# esp8266_analog_read.net
KiCad netlist of a schematic drawn in EAGLE
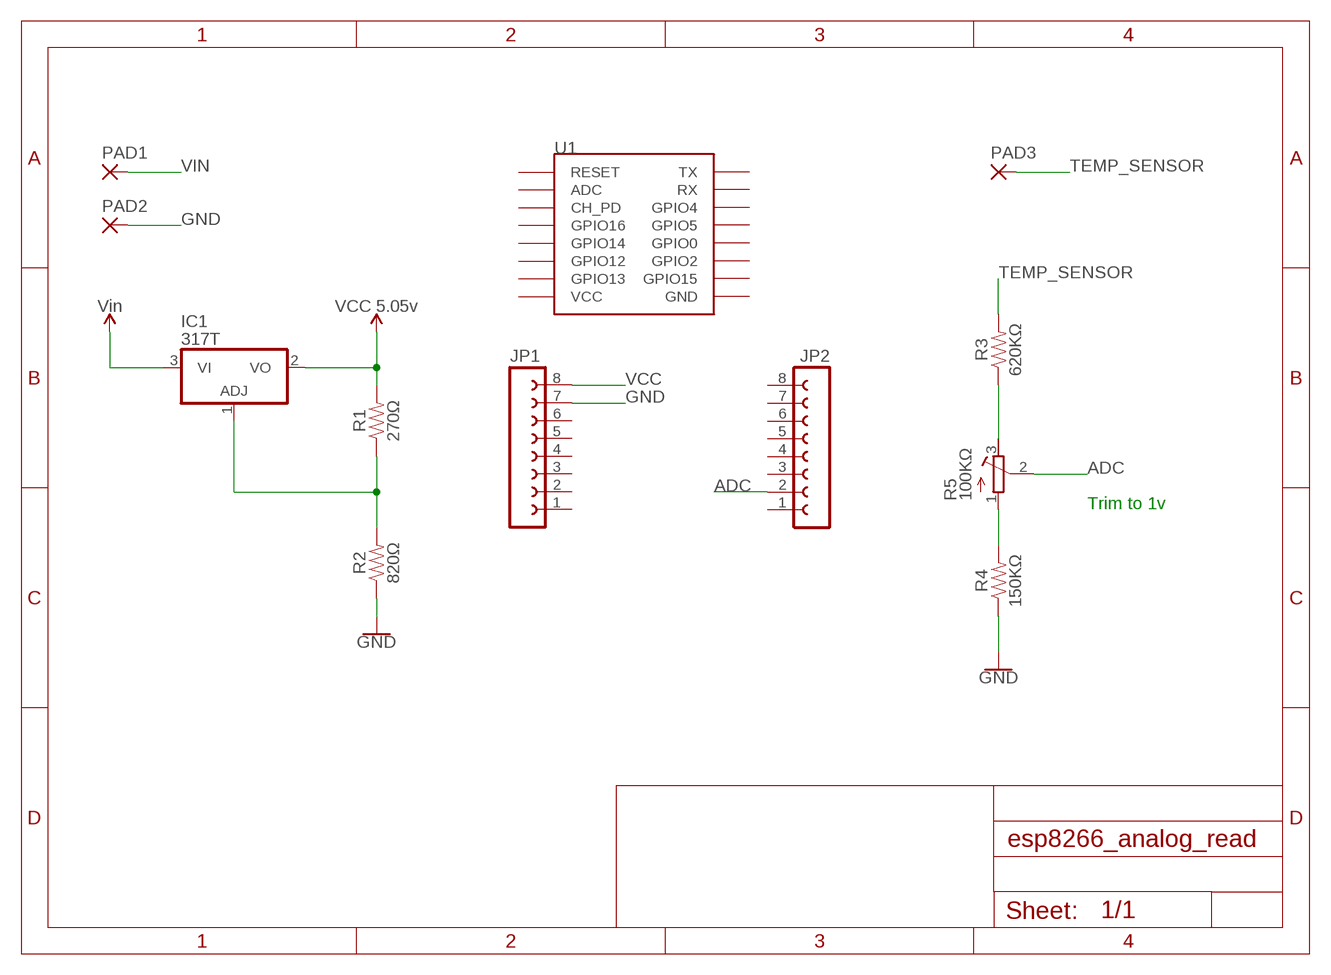
[diagram p0: schematic, sheet 1]

(export (version "E")
  (design (tool "Eeschema 10.0.6"))
  (components
    (comp (ref "IC1")
      (value "317T")
      (footprint "eagle-import:TO220H")
      (libsource (lib "eagle-import") (part "317T"))
    )
    (comp (ref "JP1")
      (value "FE08-1")
      (footprint "eagle-import:FE08")
      (libsource (lib "eagle-import") (part "FE08-1"))
    )
    (comp (ref "JP2")
      (value "FE08-1")
      (footprint "eagle-import:FE08")
      (libsource (lib "eagle-import") (part "FE08-1"))
    )
    (comp (ref "PAD1")
      (value "2,54/1,0")
      (footprint "eagle-import:2,54_1,0")
      (libsource (lib "eagle-import") (part "2,54/1,0"))
    )
    (comp (ref "PAD2")
      (value "2,54/1,0")
      (footprint "eagle-import:2,54_1,0")
      (libsource (lib "eagle-import") (part "2,54/1,0"))
    )
    (comp (ref "PAD3")
      (value "2,54/1,0")
      (footprint "eagle-import:2,54_1,0")
      (libsource (lib "eagle-import") (part "2,54/1,0"))
    )
    (comp (ref "R1")
      (value "270Ω")
      (footprint "eagle-import:AXIAL-0.3")
      (libsource (lib "eagle-import") (part "RESISTORAXIAL-0.3"))
    )
    (comp (ref "R2")
      (value "820Ω")
      (footprint "eagle-import:AXIAL-0.3")
      (libsource (lib "eagle-import") (part "RESISTORAXIAL-0.3"))
    )
    (comp (ref "R3")
      (value "620KΩ")
      (footprint "eagle-import:AXIAL-0.3")
      (libsource (lib "eagle-import") (part "RESISTORAXIAL-0.3"))
    )
    (comp (ref "R4")
      (value "150KΩ")
      (footprint "eagle-import:AXIAL-0.3")
      (libsource (lib "eagle-import") (part "RESISTORAXIAL-0.3"))
    )
    (comp (ref "R5")
      (value "100KΩ")
      (footprint "eagle-import:RTRIM3339P")
      (libsource (lib "eagle-import") (part "R-TRIMM3339P"))
    )
    (comp (ref "U1")
      (value "ESP12")
      (footprint "eagle-import:ESP12")
      (libsource (lib "eagle-import") (part "ESP12"))
    )
  )
  (nets
    (net (code "1") (name "/ADC") (class "Default")
      (node (ref "JP2") (pin "2") (pinfunction "2_2") (pintype "passive"))
      (node (ref "R5") (pin "2") (pinfunction "S_2") (pintype "passive"))
    )
    (net (code "2") (name "/TEMP_SENSOR") (class "Default")
      (node (ref "PAD3") (pin "1") (pinfunction "P_1") (pintype "passive"))
      (node (ref "R3") (pin "P$2") (pinfunction "2_P$2") (pintype "passive"))
    )
    (net (code "3") (name "GND") (class "Default")
      (node (ref "JP1") (pin "7") (pinfunction "7_7") (pintype "passive"))
      (node (ref "PAD2") (pin "1") (pinfunction "P_1") (pintype "passive"))
      (node (ref "R2") (pin "P$1") (pinfunction "1_P$1") (pintype "passive"))
      (node (ref "R4") (pin "P$1") (pinfunction "1_P$1") (pintype "passive"))
    )
    (net (code "4") (name "Net-(IC1-ADJ)") (class "Default")
      (node (ref "IC1") (pin "1") (pinfunction "ADJ_1") (pintype "input"))
      (node (ref "R1") (pin "P$1") (pinfunction "1_P$1") (pintype "passive"))
      (node (ref "R2") (pin "P$2") (pinfunction "2_P$2") (pintype "passive"))
    )
    (net (code "5") (name "Net-(R3-1)") (class "Default")
      (node (ref "R3") (pin "P$1") (pinfunction "1_P$1") (pintype "passive"))
      (node (ref "R5") (pin "3") (pinfunction "E_3") (pintype "passive"))
    )
    (net (code "6") (name "Net-(R4-2)") (class "Default")
      (node (ref "R4") (pin "P$2") (pinfunction "2_P$2") (pintype "passive"))
      (node (ref "R5") (pin "1") (pinfunction "A_1") (pintype "passive"))
    )
    (net (code "7") (name "VCC 5.05v") (class "Default")
      (node (ref "IC1") (pin "2") (pinfunction "VO_2") (pintype "passive"))
      (node (ref "JP1") (pin "8") (pinfunction "8_8") (pintype "passive"))
      (node (ref "R1") (pin "P$2") (pinfunction "2_P$2") (pintype "passive"))
    )
    (net (code "8") (name "Vin") (class "Default")
      (node (ref "IC1") (pin "3") (pinfunction "VI_3") (pintype "input"))
      (node (ref "PAD1") (pin "1") (pinfunction "P_1") (pintype "passive"))
    )
    (net (code "9") (name "unconnected-(JP1-Pad1)") (class "Default")
      (node (ref "JP1") (pin "1") (pinfunction "1_1") (pintype "passive"))
    )
    (net (code "10") (name "unconnected-(JP1-Pad2)") (class "Default")
      (node (ref "JP1") (pin "2") (pinfunction "2_2") (pintype "passive"))
    )
    (net (code "11") (name "unconnected-(JP1-Pad3)") (class "Default")
      (node (ref "JP1") (pin "3") (pinfunction "3_3") (pintype "passive"))
    )
    (net (code "12") (name "unconnected-(JP1-Pad4)") (class "Default")
      (node (ref "JP1") (pin "4") (pinfunction "4_4") (pintype "passive"))
    )
    (net (code "13") (name "unconnected-(JP1-Pad5)") (class "Default")
      (node (ref "JP1") (pin "5") (pinfunction "5_5") (pintype "passive"))
    )
    (net (code "14") (name "unconnected-(JP1-Pad6)") (class "Default")
      (node (ref "JP1") (pin "6") (pinfunction "6_6") (pintype "passive"))
    )
    (net (code "15") (name "unconnected-(JP2-Pad1)") (class "Default")
      (node (ref "JP2") (pin "1") (pinfunction "1_1") (pintype "passive"))
    )
    (net (code "16") (name "unconnected-(JP2-Pad3)") (class "Default")
      (node (ref "JP2") (pin "3") (pinfunction "3_3") (pintype "passive"))
    )
    (net (code "17") (name "unconnected-(JP2-Pad4)") (class "Default")
      (node (ref "JP2") (pin "4") (pinfunction "4_4") (pintype "passive"))
    )
    (net (code "18") (name "unconnected-(JP2-Pad5)") (class "Default")
      (node (ref "JP2") (pin "5") (pinfunction "5_5") (pintype "passive"))
    )
    (net (code "19") (name "unconnected-(JP2-Pad6)") (class "Default")
      (node (ref "JP2") (pin "6") (pinfunction "6_6") (pintype "passive"))
    )
    (net (code "20") (name "unconnected-(JP2-Pad7)") (class "Default")
      (node (ref "JP2") (pin "7") (pinfunction "7_7") (pintype "passive"))
    )
    (net (code "21") (name "unconnected-(JP2-Pad8)") (class "Default")
      (node (ref "JP2") (pin "8") (pinfunction "8_8") (pintype "passive"))
    )
    (net (code "22") (name "unconnected-(U1-PadADC)") (class "Default")
      (node (ref "U1") (pin "ADC") (pinfunction "ADC_ADC") (pintype "bidirectional"))
    )
    (net (code "23") (name "unconnected-(U1-PadCH_PD)") (class "Default")
      (node (ref "U1") (pin "CH_PD") (pinfunction "CH_PD_CH_PD") (pintype "bidirectional"))
    )
    (net (code "24") (name "unconnected-(U1-PadGND)") (class "Default")
      (node (ref "U1") (pin "GND") (pinfunction "GND_GND") (pintype "bidirectional"))
    )
    (net (code "25") (name "unconnected-(U1-PadGPIO0)") (class "Default")
      (node (ref "U1") (pin "GPIO0") (pinfunction "GPIO0_GPIO0") (pintype "bidirectional"))
    )
    (net (code "26") (name "unconnected-(U1-PadGPIO2)") (class "Default")
      (node (ref "U1") (pin "GPIO2") (pinfunction "GPIO2_GPIO2") (pintype "bidirectional"))
    )
    (net (code "27") (name "unconnected-(U1-PadGPIO4)") (class "Default")
      (node (ref "U1") (pin "GPIO4") (pinfunction "GPIO4_GPIO4") (pintype "bidirectional"))
    )
    (net (code "28") (name "unconnected-(U1-PadGPIO5)") (class "Default")
      (node (ref "U1") (pin "GPIO5") (pinfunction "GPIO5_GPIO5") (pintype "bidirectional"))
    )
    (net (code "29") (name "unconnected-(U1-PadGPIO12)") (class "Default")
      (node (ref "U1") (pin "GPIO12") (pinfunction "GPIO12_GPIO12") (pintype "bidirectional"))
    )
    (net (code "30") (name "unconnected-(U1-PadGPIO13)") (class "Default")
      (node (ref "U1") (pin "GPIO13") (pinfunction "GPIO13_GPIO13") (pintype "bidirectional"))
    )
    (net (code "31") (name "unconnected-(U1-PadGPIO14)") (class "Default")
      (node (ref "U1") (pin "GPIO14") (pinfunction "GPIO14_GPIO14") (pintype "bidirectional"))
    )
    (net (code "32") (name "unconnected-(U1-PadGPIO15)") (class "Default")
      (node (ref "U1") (pin "GPIO15") (pinfunction "GPIO15_GPIO15") (pintype "bidirectional"))
    )
    (net (code "33") (name "unconnected-(U1-PadGPIO16)") (class "Default")
      (node (ref "U1") (pin "GPIO16") (pinfunction "GPIO16_GPIO16") (pintype "bidirectional"))
    )
    (net (code "34") (name "unconnected-(U1-PadRESET)") (class "Default")
      (node (ref "U1") (pin "RESET") (pinfunction "RESET_RESET") (pintype "bidirectional"))
    )
    (net (code "35") (name "unconnected-(U1-PadRX)") (class "Default")
      (node (ref "U1") (pin "RX") (pinfunction "RX_RX") (pintype "bidirectional"))
    )
    (net (code "36") (name "unconnected-(U1-PadTX)") (class "Default")
      (node (ref "U1") (pin "TX") (pinfunction "TX_TX") (pintype "bidirectional"))
    )
    (net (code "37") (name "unconnected-(U1-PadVCC)") (class "Default")
      (node (ref "U1") (pin "VCC") (pinfunction "VCC_VCC") (pintype "bidirectional"))
    )
  )
)
